# COREv1_4.net
KiCad netlist of a schematic drawn in Altium Designer
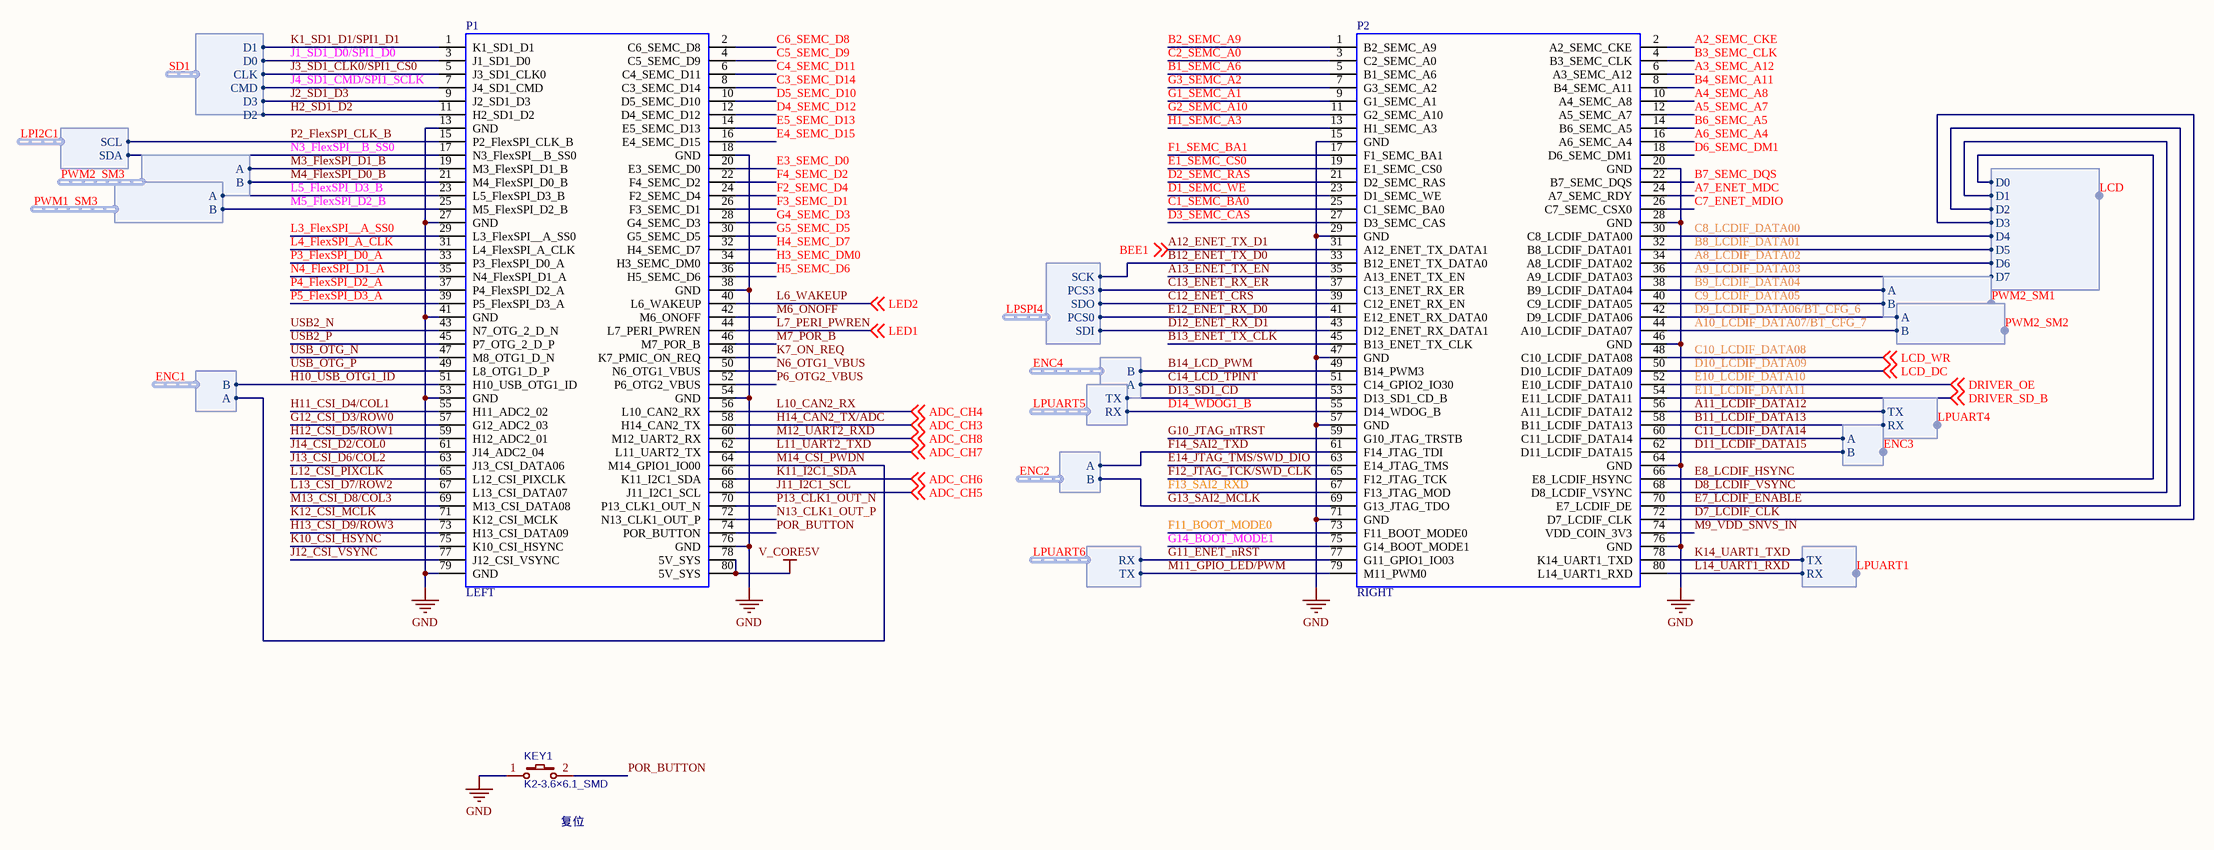
[diagram p0: COREv1.4.SchDoc]

(export (version "E")
  (design (tool "Eeschema 10.0.6"))
  (components
    (comp (ref "KEY1")
      (value "K2-3.6×6.1_SMD")
      (footprint "KEY-SMD_2P-L6.2-W3.6-LS8.0")
      (fields
        (field (name "BOM_SUPPLIER PART") "C118141")
        (field (name "BOM_MANUFACTURER PART") "K2-1107ST-A4SW-06")
        (field (name "CONTRIBUTOR") "LCEDA_Lib")
      )
      (libsource (lib "JLC") (part "K2-3.6×6.1_SMD"))
    )
    (comp (ref "P1")
      (value "LEFT")
      (footprint "CON80")
      (description "Header, 30-Pin, Dual row")
      (fields (field (name "PUBLISHER") "Altium Limited"))
      (libsource (lib "OK1050-C V1.2_B") (part "Header40X2_left"))
    )
    (comp (ref "P2")
      (value "RIGHT")
      (footprint "CON80")
      (description "Header, 30-Pin, Dual row")
      (fields (field (name "PUBLISHER") "Altium Limited"))
      (libsource (lib "OK1050-C V1.2_B") (part "Header40X2_right"))
    )
  )
  (nets
    (net (code "11") (name "/A2_SEMC_CKE") (class "Default")
      (node (ref "P2") (pin "2") (pinfunction "A2_SEMC_CKE_2") (pintype "passive"))
    )
    (net (code "12") (name "/A3_SEMC_A12") (class "Default")
      (node (ref "P2") (pin "6") (pinfunction "A3_SEMC_A12_6") (pintype "passive"))
    )
    (net (code "13") (name "/A4_SEMC_A8") (class "Default")
      (node (ref "P2") (pin "10") (pinfunction "A4_SEMC_A8_10") (pintype "passive"))
    )
    (net (code "14") (name "/A5_SEMC_A7") (class "Default")
      (node (ref "P2") (pin "12") (pinfunction "A5_SEMC_A7_12") (pintype "passive"))
    )
    (net (code "15") (name "/A6_SEMC_A4") (class "Default")
      (node (ref "P2") (pin "16") (pinfunction "A6_SEMC_A4_16") (pintype "passive"))
    )
    (net (code "16") (name "/A7_ENET_MDC") (class "Default")
      (node (ref "P2") (pin "24") (pinfunction "A7_SEMC_RDY_24") (pintype "passive"))
    )
    (net (code "17") (name "/A8_LCDIF_DATA02") (class "Default")
      (node (ref "P2") (pin "34") (pinfunction "A8_LCDIF_DATA02_34") (pintype "passive"))
    )
    (net (code "18") (name "/A9_LCDIF_DATA03") (class "Default")
      (node (ref "P2") (pin "36") (pinfunction "A9_LCDIF_DATA03_36") (pintype "passive"))
    )
    (net (code "19") (name "/A10_LCDIF_DATA07{slash}BT_CFG_7") (class "Default")
      (node (ref "P2") (pin "44") (pinfunction "A10_LCDIF_DATA07_44") (pintype "passive"))
    )
    (net (code "20") (name "/A11_LCDIF_DATA12") (class "Default")
      (node (ref "P2") (pin "56") (pinfunction "A11_LCDIF_DATA12_56") (pintype "passive"))
    )
    (net (code "21") (name "/A13_ENET_TX_EN") (class "Default")
      (node (ref "P2") (pin "35") (pinfunction "A13_ENET_TX_EN_35") (pintype "passive"))
    )
    (net (code "22") (name "/B1_SEMC_A6") (class "Default")
      (node (ref "P2") (pin "5") (pinfunction "B1_SEMC_A6_5") (pintype "passive"))
    )
    (net (code "23") (name "/B2_SEMC_A9") (class "Default")
      (node (ref "P2") (pin "1") (pinfunction "B2_SEMC_A9_1") (pintype "passive"))
    )
    (net (code "24") (name "/B3_SEMC_CLK") (class "Default")
      (node (ref "P2") (pin "4") (pinfunction "B3_SEMC_CLK_4") (pintype "passive"))
    )
    (net (code "25") (name "/B4_SEMC_A11") (class "Default")
      (node (ref "P2") (pin "8") (pinfunction "B4_SEMC_A11_8") (pintype "passive"))
    )
    (net (code "26") (name "/B6_SEMC_A5") (class "Default")
      (node (ref "P2") (pin "14") (pinfunction "B6_SEMC_A5_14") (pintype "passive"))
    )
    (net (code "27") (name "/B7_SEMC_DQS") (class "Default")
      (node (ref "P2") (pin "22") (pinfunction "B7_SEMC_DQS_22") (pintype "passive"))
    )
    (net (code "28") (name "/B8_LCDIF_DATA01") (class "Default")
      (node (ref "P2") (pin "32") (pinfunction "B8_LCDIF_DATA01_32") (pintype "passive"))
    )
    (net (code "29") (name "/B9_LCDIF_DATA04") (class "Default")
      (node (ref "P2") (pin "38") (pinfunction "B9_LCDIF_DATA04_38") (pintype "passive"))
    )
    (net (code "30") (name "/B11_LCDIF_DATA13") (class "Default")
      (node (ref "P2") (pin "58") (pinfunction "B11_LCDIF_DATA13_58") (pintype "passive"))
    )
    (net (code "31") (name "/B12_ENET_TX_D0") (class "Default")
      (node (ref "P2") (pin "33") (pinfunction "B12_ENET_TX_DATA0_33") (pintype "passive"))
    )
    (net (code "32") (name "/B13_ENET_TX_CLK") (class "Default")
      (node (ref "P2") (pin "45") (pinfunction "B13_ENET_TX_CLK_45") (pintype "passive"))
    )
    (net (code "33") (name "/B14_LCD_PWM") (class "Default")
      (node (ref "P2") (pin "49") (pinfunction "B14_PWM3_49") (pintype "passive"))
    )
    (net (code "34") (name "/C1_SEMC_BA0") (class "Default")
      (node (ref "P2") (pin "25") (pinfunction "C1_SEMC_BA0_25") (pintype "passive"))
    )
    (net (code "35") (name "/C2_SEMC_A0") (class "Default")
      (node (ref "P2") (pin "3") (pinfunction "C2_SEMC_A0_3") (pintype "passive"))
    )
    (net (code "36") (name "/C3_SEMC_D14") (class "Default")
      (node (ref "P1") (pin "8") (pinfunction "C3_SEMC_D14_8") (pintype "passive"))
    )
    (net (code "37") (name "/C4_SEMC_D11") (class "Default")
      (node (ref "P1") (pin "6") (pinfunction "C4_SEMC_D11_6") (pintype "passive"))
    )
    (net (code "38") (name "/C5_SEMC_D9") (class "Default")
      (node (ref "P1") (pin "4") (pinfunction "C5_SEMC_D9_4") (pintype "passive"))
    )
    (net (code "39") (name "/C6_SEMC_D8") (class "Default")
      (node (ref "P1") (pin "2") (pinfunction "C6_SEMC_D8_2") (pintype "passive"))
    )
    (net (code "40") (name "/C7_ENET_MDIO") (class "Default")
      (node (ref "P2") (pin "26") (pinfunction "C7_SEMC_CSX0_26") (pintype "passive"))
    )
    (net (code "41") (name "/C8_LCDIF_DATA00") (class "Default")
      (node (ref "P2") (pin "30") (pinfunction "C8_LCDIF_DATA00_30") (pintype "passive"))
    )
    (net (code "42") (name "/C9_LCDIF_DATA05") (class "Default")
      (node (ref "P2") (pin "40") (pinfunction "C9_LCDIF_DATA05_40") (pintype "passive"))
    )
    (net (code "43") (name "/C11_LCDIF_DATA14") (class "Default")
      (node (ref "P2") (pin "60") (pinfunction "C11_LCDIF_DATA14_60") (pintype "passive"))
    )
    (net (code "44") (name "/C12_ENET_CRS") (class "Default")
      (node (ref "P2") (pin "39") (pinfunction "C12_ENET_RX_EN_39") (pintype "passive"))
    )
    (net (code "45") (name "/C13_ENET_RX_ER") (class "Default")
      (node (ref "P2") (pin "37") (pinfunction "C13_ENET_RX_ER_37") (pintype "passive"))
    )
    (net (code "46") (name "/C14_LCD_TPINT") (class "Default")
      (node (ref "P2") (pin "51") (pinfunction "C14_GPIO2_IO30_51") (pintype "passive"))
    )
    (net (code "47") (name "/D1_SEMC_WE") (class "Default")
      (node (ref "P2") (pin "23") (pinfunction "D1_SEMC_WE_23") (pintype "passive"))
    )
    (net (code "48") (name "/D2_SEMC_RAS") (class "Default")
      (node (ref "P2") (pin "21") (pinfunction "D2_SEMC_RAS_21") (pintype "passive"))
    )
    (net (code "49") (name "/D3_SEMC_CAS") (class "Default")
      (node (ref "P2") (pin "27") (pinfunction "D3_SEMC_CAS_27") (pintype "passive"))
    )
    (net (code "50") (name "/D4_SEMC_D12") (class "Default")
      (node (ref "P1") (pin "12") (pinfunction "D4_SEMC_D12_12") (pintype "passive"))
    )
    (net (code "51") (name "/D5_SEMC_D10") (class "Default")
      (node (ref "P1") (pin "10") (pinfunction "D5_SEMC_D10_10") (pintype "passive"))
    )
    (net (code "52") (name "/D6_SEMC_DM1") (class "Default")
      (node (ref "P2") (pin "18") (pinfunction "D6_SEMC_DM1_18") (pintype "passive"))
    )
    (net (code "53") (name "/D7_LCDIF_CLK") (class "Default")
      (node (ref "P2") (pin "72") (pinfunction "D7_LCDIF_CLK_72") (pintype "passive"))
    )
    (net (code "54") (name "/D8_LCDIF_VSYNC") (class "Default")
      (node (ref "P2") (pin "68") (pinfunction "D8_LCDIF_VSYNC_68") (pintype "passive"))
    )
    (net (code "55") (name "/D9_LCDIF_DATA06{slash}BT_CFG_6") (class "Default")
      (node (ref "P2") (pin "42") (pinfunction "D9_LCDIF_DATA06_42") (pintype "passive"))
    )
    (net (code "56") (name "/D11_LCDIF_DATA15") (class "Default")
      (node (ref "P2") (pin "62") (pinfunction "D11_LCDIF_DATA15_62") (pintype "passive"))
    )
    (net (code "57") (name "/D12_ENET_RX_D1") (class "Default")
      (node (ref "P2") (pin "43") (pinfunction "D12_ENET_RX_DATA1_43") (pintype "passive"))
    )
    (net (code "58") (name "/D13_SD1_CD") (class "Default")
      (node (ref "P2") (pin "53") (pinfunction "D13_SD1_CD_B_53") (pintype "passive"))
    )
    (net (code "59") (name "/D14_WDOG1_B") (class "Default")
      (node (ref "P2") (pin "55") (pinfunction "D14_WDOG_B_55") (pintype "passive"))
    )
    (net (code "60") (name "/E1_SEMC_CS0") (class "Default")
      (node (ref "P2") (pin "19") (pinfunction "E1_SEMC_CS0_19") (pintype "passive"))
    )
    (net (code "61") (name "/E3_SEMC_D0") (class "Default")
      (node (ref "P1") (pin "20") (pinfunction "E3_SEMC_D0_20") (pintype "passive"))
    )
    (net (code "62") (name "/E4_SEMC_D15") (class "Default")
      (node (ref "P1") (pin "16") (pinfunction "E4_SEMC_D15_16") (pintype "passive"))
    )
    (net (code "63") (name "/E5_SEMC_D13") (class "Default")
      (node (ref "P1") (pin "14") (pinfunction "E5_SEMC_D13_14") (pintype "passive"))
    )
    (net (code "64") (name "/E7_LCDIF_ENABLE") (class "Default")
      (node (ref "P2") (pin "70") (pinfunction "E7_LCDIF_DE_70") (pintype "passive"))
    )
    (net (code "65") (name "/E8_LCDIF_HSYNC") (class "Default")
      (node (ref "P2") (pin "66") (pinfunction "E8_LCDIF_HSYNC_66") (pintype "passive"))
    )
    (net (code "66") (name "/E12_ENET_RX_D0") (class "Default")
      (node (ref "P2") (pin "41") (pinfunction "E12_ENET_RX_DATA0_41") (pintype "passive"))
    )
    (net (code "67") (name "/E14_JTAG_TMS{slash}SWD_DIO") (class "Default")
      (node (ref "P2") (pin "63") (pinfunction "E14_JTAG_TMS_63") (pintype "passive"))
    )
    (net (code "72") (name "/F1_SEMC_BA1") (class "Default")
      (node (ref "P2") (pin "17") (pinfunction "F1_SEMC_BA1_17") (pintype "passive"))
    )
    (net (code "73") (name "/F2_SEMC_D4") (class "Default")
      (node (ref "P1") (pin "24") (pinfunction "F2_SEMC_D4_24") (pintype "passive"))
    )
    (net (code "74") (name "/F3_SEMC_D1") (class "Default")
      (node (ref "P1") (pin "26") (pinfunction "F3_SEMC_D1_26") (pintype "passive"))
    )
    (net (code "75") (name "/F4_SEMC_D2") (class "Default")
      (node (ref "P1") (pin "22") (pinfunction "F4_SEMC_D2_22") (pintype "passive"))
    )
    (net (code "76") (name "/F11_BOOT_MODE0") (class "Default")
      (node (ref "P2") (pin "73") (pinfunction "F11_BOOT_MODE0_73") (pintype "passive"))
    )
    (net (code "77") (name "/F12_JTAG_TCK{slash}SWD_CLK") (class "Default")
      (node (ref "P2") (pin "65") (pinfunction "F12_JTAG_TCK_65") (pintype "passive"))
    )
    (net (code "78") (name "/F13_SAI2_RXD") (class "Default")
      (node (ref "P2") (pin "67") (pinfunction "F13_JTAG_MOD_67") (pintype "passive"))
    )
    (net (code "79") (name "/F14_SAI2_TXD") (class "Default")
      (node (ref "P2") (pin "61") (pinfunction "F14_JTAG_TDI_61") (pintype "passive"))
    )
    (net (code "80") (name "/G1_SEMC_A1") (class "Default")
      (node (ref "P2") (pin "9") (pinfunction "G1_SEMC_A1_9") (pintype "passive"))
    )
    (net (code "81") (name "/G2_SEMC_A10") (class "Default")
      (node (ref "P2") (pin "11") (pinfunction "G2_SEMC_A10_11") (pintype "passive"))
    )
    (net (code "82") (name "/G3_SEMC_A2") (class "Default")
      (node (ref "P2") (pin "7") (pinfunction "G3_SEMC_A2_7") (pintype "passive"))
    )
    (net (code "83") (name "/G4_SEMC_D3") (class "Default")
      (node (ref "P1") (pin "28") (pinfunction "G4_SEMC_D3_28") (pintype "passive"))
    )
    (net (code "84") (name "/G5_SEMC_D5") (class "Default")
      (node (ref "P1") (pin "30") (pinfunction "G5_SEMC_D5_30") (pintype "passive"))
    )
    (net (code "85") (name "/G10_JTAG_nTRST") (class "Default")
      (node (ref "P2") (pin "59") (pinfunction "G10_JTAG_TRSTB_59") (pintype "passive"))
    )
    (net (code "86") (name "/G11_ENET_nRST") (class "Default")
      (node (ref "P2") (pin "77") (pinfunction "G11_GPIO1_IO03_77") (pintype "passive"))
    )
    (net (code "87") (name "/G12_CSI_D3{slash}ROW0") (class "Default")
      (node (ref "P1") (pin "57") (pinfunction "G12_ADC2_03_57") (pintype "passive"))
    )
    (net (code "88") (name "/G13_SAI2_MCLK") (class "Default")
      (node (ref "P2") (pin "69") (pinfunction "G13_JTAG_TDO_69") (pintype "passive"))
    )
    (net (code "89") (name "/G14_BOOT_MODE1") (class "Default")
      (node (ref "P2") (pin "75") (pinfunction "G14_BOOT_MODE1_75") (pintype "passive"))
    )
    (net (code "90") (name "/H1_SEMC_A3") (class "Default")
      (node (ref "P2") (pin "13") (pinfunction "H1_SEMC_A3_13") (pintype "passive"))
    )
    (net (code "91") (name "/H2_SD1_D2") (class "Default")
      (node (ref "P1") (pin "11") (pinfunction "H2_SD1_D2_11") (pintype "passive"))
    )
    (net (code "92") (name "/H3_SEMC_DM0") (class "Default")
      (node (ref "P1") (pin "34") (pinfunction "H3_SEMC_DM0_34") (pintype "passive"))
    )
    (net (code "93") (name "/H4_SEMC_D7") (class "Default")
      (node (ref "P1") (pin "32") (pinfunction "H4_SEMC_D7_32") (pintype "passive"))
    )
    (net (code "94") (name "/H5_SEMC_D6") (class "Default")
      (node (ref "P1") (pin "36") (pinfunction "H5_SEMC_D6_36") (pintype "passive"))
    )
    (net (code "95") (name "/H10_USB_OTG1_ID") (class "Default")
      (node (ref "P1") (pin "51") (pinfunction "H10_USB_OTG1_ID_51") (pintype "passive"))
    )
    (net (code "96") (name "/H11_CSI_D4{slash}COL1") (class "Default")
      (node (ref "P1") (pin "55") (pinfunction "H11_ADC2_02_55") (pintype "passive"))
    )
    (net (code "97") (name "/H12_CSI_D5{slash}ROW1") (class "Default")
      (node (ref "P1") (pin "59") (pinfunction "H12_ADC2_01_59") (pintype "passive"))
    )
    (net (code "98") (name "/H13_CSI_D9{slash}ROW3") (class "Default")
      (node (ref "P1") (pin "73") (pinfunction "H13_CSI_DATA09_73") (pintype "passive"))
    )
    (net (code "99") (name "/J1_SD1_D0{slash}SPI1_D0") (class "Default")
      (node (ref "P1") (pin "3") (pinfunction "J1_SD1_D0_3") (pintype "passive"))
    )
    (net (code "100") (name "/J2_SD1_D3") (class "Default")
      (node (ref "P1") (pin "9") (pinfunction "J2_SD1_D3_9") (pintype "passive"))
    )
    (net (code "101") (name "/J3_SD1_CLK0{slash}SPI1_CS0") (class "Default")
      (node (ref "P1") (pin "5") (pinfunction "J3_SD1_CLK0_5") (pintype "passive"))
    )
    (net (code "102") (name "/J4_SD1_CMD{slash}SPI1_SCLK") (class "Default")
      (node (ref "P1") (pin "7") (pinfunction "J4_SD1_CMD_7") (pintype "passive"))
    )
    (net (code "103") (name "/J12_CSI_VSYNC") (class "Default")
      (node (ref "P1") (pin "77") (pinfunction "J12_CSI_VSYNC_77") (pintype "passive"))
    )
    (net (code "104") (name "/J13_CSI_D6{slash}COL2") (class "Default")
      (node (ref "P1") (pin "63") (pinfunction "J13_CSI_DATA06_63") (pintype "passive"))
    )
    (net (code "105") (name "/J14_CSI_D2{slash}COL0") (class "Default")
      (node (ref "P1") (pin "61") (pinfunction "J14_ADC2_04_61") (pintype "passive"))
    )
    (net (code "106") (name "/K1_SD1_D1{slash}SPI1_D1") (class "Default")
      (node (ref "P1") (pin "1") (pinfunction "K1_SD1_D1_1") (pintype "passive"))
    )
    (net (code "107") (name "/K7_ON_REQ") (class "Default")
      (node (ref "P1") (pin "48") (pinfunction "K7_PMIC_ON_REQ_48") (pintype "passive"))
    )
    (net (code "108") (name "/K10_CSI_HSYNC") (class "Default")
      (node (ref "P1") (pin "75") (pinfunction "K10_CSI_HSYNC_75") (pintype "passive"))
    )
    (net (code "109") (name "/K12_CSI_MCLK") (class "Default")
      (node (ref "P1") (pin "71") (pinfunction "K12_CSI_MCLK_71") (pintype "passive"))
    )
    (net (code "110") (name "/K14_UART1_TXD") (class "Default")
      (node (ref "P2") (pin "78") (pinfunction "K14_UART1_TXD_78") (pintype "passive"))
    )
    (net (code "111") (name "/L3_FlexSPI__A_SS0") (class "Default")
      (node (ref "P1") (pin "29") (pinfunction "L3_FlexSPI__A_SS0_29") (pintype "passive"))
    )
    (net (code "112") (name "/L4_FlexSPI_A_CLK") (class "Default")
      (node (ref "P1") (pin "31") (pinfunction "L4_FlexSPI_A_CLK_31") (pintype "passive"))
    )
    (net (code "113") (name "/L5_FlexSPI_D3_B") (class "Default")
      (node (ref "P1") (pin "23") (pinfunction "L5_FlexSPI_D3_B_23") (pintype "passive"))
    )
    (net (code "114") (name "/L12_CSI_PIXCLK") (class "Default")
      (node (ref "P1") (pin "65") (pinfunction "L12_CSI_PIXCLK_65") (pintype "passive"))
    )
    (net (code "115") (name "/L13_CSI_D7{slash}ROW2") (class "Default")
      (node (ref "P1") (pin "67") (pinfunction "L13_CSI_DATA07_67") (pintype "passive"))
    )
    (net (code "116") (name "/L14_UART1_RXD") (class "Default")
      (node (ref "P2") (pin "80") (pinfunction "L14_UART1_RXD_80") (pintype "passive"))
    )
    (net (code "124") (name "/M3_FlexSPI_D1_B") (class "Default")
      (node (ref "P1") (pin "19") (pinfunction "M3_FlexSPI_D1_B_19") (pintype "passive"))
    )
    (net (code "125") (name "/M4_FlexSPI_D0_B") (class "Default")
      (node (ref "P1") (pin "21") (pinfunction "M4_FlexSPI_D0_B_21") (pintype "passive"))
    )
    (net (code "126") (name "/M5_FlexSPI_D2_B") (class "Default")
      (node (ref "P1") (pin "25") (pinfunction "M5_FlexSPI_D2_B_25") (pintype "passive"))
    )
    (net (code "127") (name "/M6_ONOFF") (class "Default")
      (node (ref "P1") (pin "42") (pinfunction "M6_ONOFF_42") (pintype "passive"))
    )
    (net (code "128") (name "/M7_POR_B") (class "Default")
      (node (ref "P1") (pin "46") (pinfunction "M7_POR_B_46") (pintype "passive"))
    )
    (net (code "129") (name "/M9_VDD_SNVS_IN") (class "Default")
      (node (ref "P2") (pin "74") (pinfunction "VDD_COIN_3V3_74") (pintype "passive"))
    )
    (net (code "130") (name "/M11_GPIO_LED{slash}PWM") (class "Default")
      (node (ref "P2") (pin "79") (pinfunction "M11_PWM0_79") (pintype "passive"))
    )
    (net (code "131") (name "/M13_CSI_D8{slash}COL3") (class "Default")
      (node (ref "P1") (pin "69") (pinfunction "M13_CSI_DATA08_69") (pintype "passive"))
    )
    (net (code "132") (name "/M14_CSI_PWDN") (class "Default")
      (node (ref "P1") (pin "64") (pinfunction "M14_GPIO1_IO00_64") (pintype "passive"))
    )
    (net (code "133") (name "/N3_FlexSPI__B_SS0") (class "Default")
      (node (ref "P1") (pin "17") (pinfunction "N3_FlexSPI__B_SS0_17") (pintype "passive"))
    )
    (net (code "134") (name "/N4_FlexSPI_D1_A") (class "Default")
      (node (ref "P1") (pin "35") (pinfunction "N4_FlexSPI_D1_A_35") (pintype "passive"))
    )
    (net (code "135") (name "/N6_OTG1_VBUS") (class "Default")
      (node (ref "P1") (pin "50") (pinfunction "N6_OTG1_VBUS_50") (pintype "passive"))
    )
    (net (code "136") (name "/N13_CLK1_OUT_P") (class "Default")
      (node (ref "P1") (pin "72") (pinfunction "N13_CLK1_OUT_P_72") (pintype "passive"))
    )
    (net (code "137") (name "/P2_FlexSPI_CLK_B") (class "Default")
      (node (ref "P1") (pin "15") (pinfunction "P2_FlexSPI_CLK_B_15") (pintype "passive"))
    )
    (net (code "138") (name "/P3_FlexSPI_D0_A") (class "Default")
      (node (ref "P1") (pin "33") (pinfunction "P3_FlexSPI_D0_A_33") (pintype "passive"))
    )
    (net (code "139") (name "/P4_FlexSPI_D2_A") (class "Default")
      (node (ref "P1") (pin "37") (pinfunction "P4_FlexSPI_D2_A_37") (pintype "passive"))
    )
    (net (code "140") (name "/P5_FlexSPI_D3_A") (class "Default")
      (node (ref "P1") (pin "39") (pinfunction "P5_FlexSPI_D3_A_39") (pintype "passive"))
    )
    (net (code "141") (name "/P6_OTG2_VBUS") (class "Default")
      (node (ref "P1") (pin "52") (pinfunction "P6_OTG2_VBUS_52") (pintype "passive"))
    )
    (net (code "142") (name "/P13_CLK1_OUT_N") (class "Default")
      (node (ref "P1") (pin "70") (pinfunction "P13_CLK1_OUT_N_70") (pintype "passive"))
    )
    (net (code "143") (name "/POR_BUTTON") (class "Default")
      (node (ref "KEY1") (pin "2") (pinfunction "2_2") (pintype "passive"))
      (node (ref "P1") (pin "74") (pinfunction "POR_BUTTON_74") (pintype "passive"))
    )
    (net (code "148") (name "/USB2_N") (class "Default")
      (node (ref "P1") (pin "43") (pinfunction "N7_OTG_2_D_N_43") (pintype "passive"))
    )
    (net (code "149") (name "/USB2_P") (class "Default")
      (node (ref "P1") (pin "45") (pinfunction "P7_OTG_2_D_P_45") (pintype "passive"))
    )
    (net (code "150") (name "/USB_OTG_N") (class "Default")
      (node (ref "P1") (pin "47") (pinfunction "M8_OTG1_D_N_47") (pintype "passive"))
    )
    (net (code "151") (name "/USB_OTG_P") (class "Default")
      (node (ref "P1") (pin "49") (pinfunction "L8_OTG1_D_P_49") (pintype "passive"))
    )
    (net (code "153") (name "ADC_CH3") (class "Default")
      (node (ref "P1") (pin "58") (pinfunction "H14_CAN2_TX_58") (pintype "passive"))
    )
    (net (code "154") (name "ADC_CH4") (class "Default")
      (node (ref "P1") (pin "56") (pinfunction "L10_CAN2_RX_56") (pintype "passive"))
    )
    (net (code "155") (name "ADC_CH5") (class "Default")
      (node (ref "P1") (pin "68") (pinfunction "J11_I2C1_SCL_68") (pintype "passive"))
    )
    (net (code "156") (name "ADC_CH6") (class "Default")
      (node (ref "P1") (pin "66") (pinfunction "K11_I2C1_SDA_66") (pintype "passive"))
    )
    (net (code "157") (name "ADC_CH7") (class "Default")
      (node (ref "P1") (pin "62") (pinfunction "L11_UART2_TX_62") (pintype "passive"))
    )
    (net (code "158") (name "ADC_CH8") (class "Default")
      (node (ref "P1") (pin "60") (pinfunction "M12_UART2_RX_60") (pintype "passive"))
    )
    (net (code "159") (name "BEE1") (class "Default")
      (node (ref "P2") (pin "31") (pinfunction "A12_ENET_TX_DATA1_31") (pintype "passive"))
    )
    (net (code "160") (name "DRIVER_OE") (class "Default")
      (node (ref "P2") (pin "52") (pinfunction "E10_LCDIF_DATA10_52") (pintype "passive"))
    )
    (net (code "161") (name "DRIVER_SD_B") (class "Default")
      (node (ref "P2") (pin "54") (pinfunction "E11_LCDIF_DATA11_54") (pintype "passive"))
    )
    (net (code "162") (name "GND") (class "Default")
      (node (ref "KEY1") (pin "1") (pinfunction "1_1") (pintype "passive"))
      (node (ref "P1") (pin "13") (pinfunction "GND_13") (pintype "passive"))
      (node (ref "P1") (pin "18") (pinfunction "GND_18") (pintype "passive"))
      (node (ref "P1") (pin "27") (pinfunction "GND_27") (pintype "passive"))
      (node (ref "P1") (pin "38") (pinfunction "GND_38") (pintype "passive"))
      (node (ref "P1") (pin "41") (pinfunction "GND_41") (pintype "passive"))
      (node (ref "P1") (pin "53") (pinfunction "GND_53") (pintype "passive"))
      (node (ref "P1") (pin "54") (pinfunction "GND_54") (pintype "passive"))
      (node (ref "P1") (pin "76") (pinfunction "GND_76") (pintype "passive"))
      (node (ref "P1") (pin "79") (pinfunction "GND_79") (pintype "passive"))
      (node (ref "P2") (pin "15") (pinfunction "GND_15") (pintype "passive"))
      (node (ref "P2") (pin "20") (pinfunction "GND_20") (pintype "passive"))
      (node (ref "P2") (pin "28") (pinfunction "GND_28") (pintype "passive"))
      (node (ref "P2") (pin "29") (pinfunction "GND_29") (pintype "passive"))
      (node (ref "P2") (pin "46") (pinfunction "GND_46") (pintype "passive"))
      (node (ref "P2") (pin "47") (pinfunction "GND_47") (pintype "passive"))
      (node (ref "P2") (pin "57") (pinfunction "GND_57") (pintype "passive"))
      (node (ref "P2") (pin "64") (pinfunction "GND_64") (pintype "passive"))
      (node (ref "P2") (pin "71") (pinfunction "GND_71") (pintype "passive"))
      (node (ref "P2") (pin "76") (pinfunction "GND_76") (pintype "passive"))
    )
    (net (code "163") (name "LCD_DC") (class "Default")
      (node (ref "P2") (pin "50") (pinfunction "D10_LCDIF_DATA09_50") (pintype "passive"))
    )
    (net (code "164") (name "LCD_WR") (class "Default")
      (node (ref "P2") (pin "48") (pinfunction "C10_LCDIF_DATA08_48") (pintype "passive"))
    )
    (net (code "165") (name "LED1") (class "Default")
      (node (ref "P1") (pin "44") (pinfunction "L7_PERI_PWREN_44") (pintype "passive"))
    )
    (net (code "166") (name "LED2") (class "Default")
      (node (ref "P1") (pin "40") (pinfunction "L6_WAKEUP_40") (pintype "passive"))
    )
    (net (code "167") (name "V_CORE5V") (class "Default")
      (node (ref "P1") (pin "78") (pinfunction "5V_SYS_78") (pintype "passive"))
      (node (ref "P1") (pin "80") (pinfunction "5V_SYS_80") (pintype "passive"))
    )
  )
)
